# ProPrj_RS485_to_TTL_Converter_2026-02-24.net
KiCad netlist of a schematic drawn in EasyEDA Pro
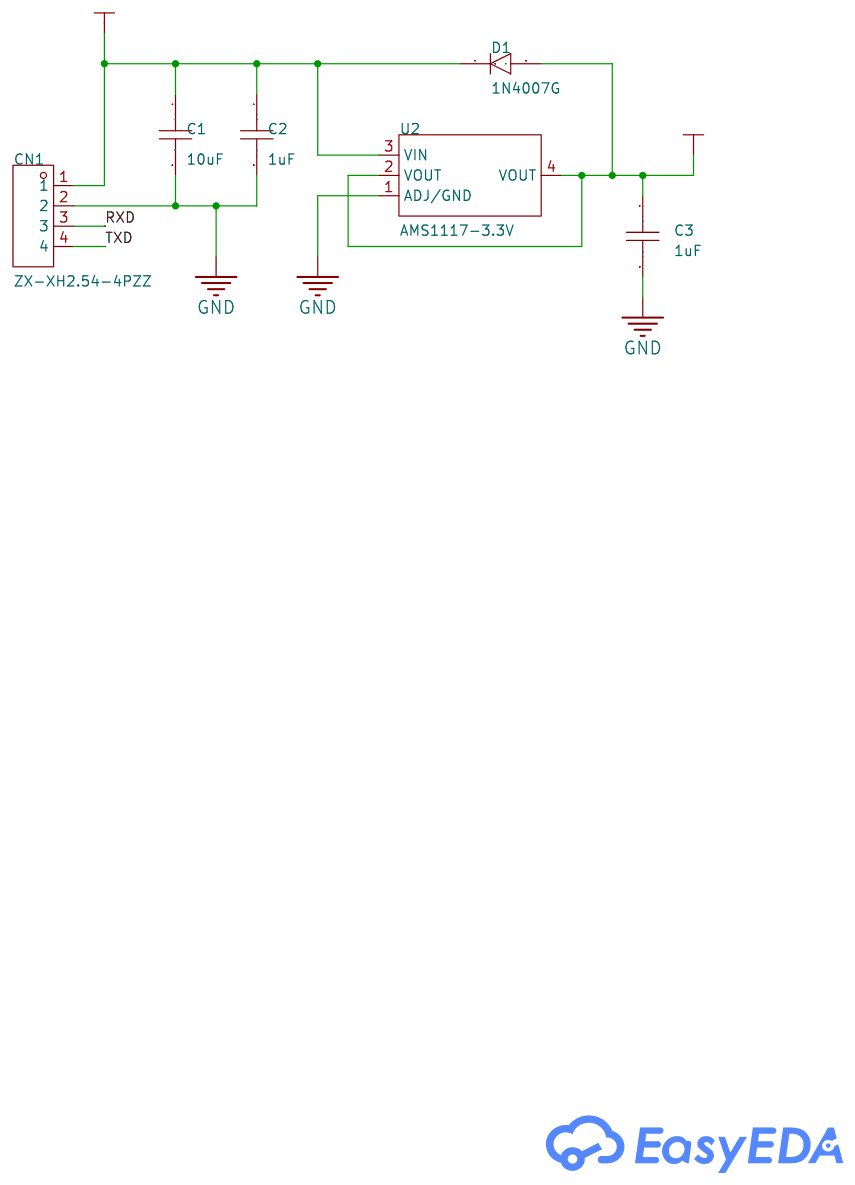
[diagram p0: Power Supply]
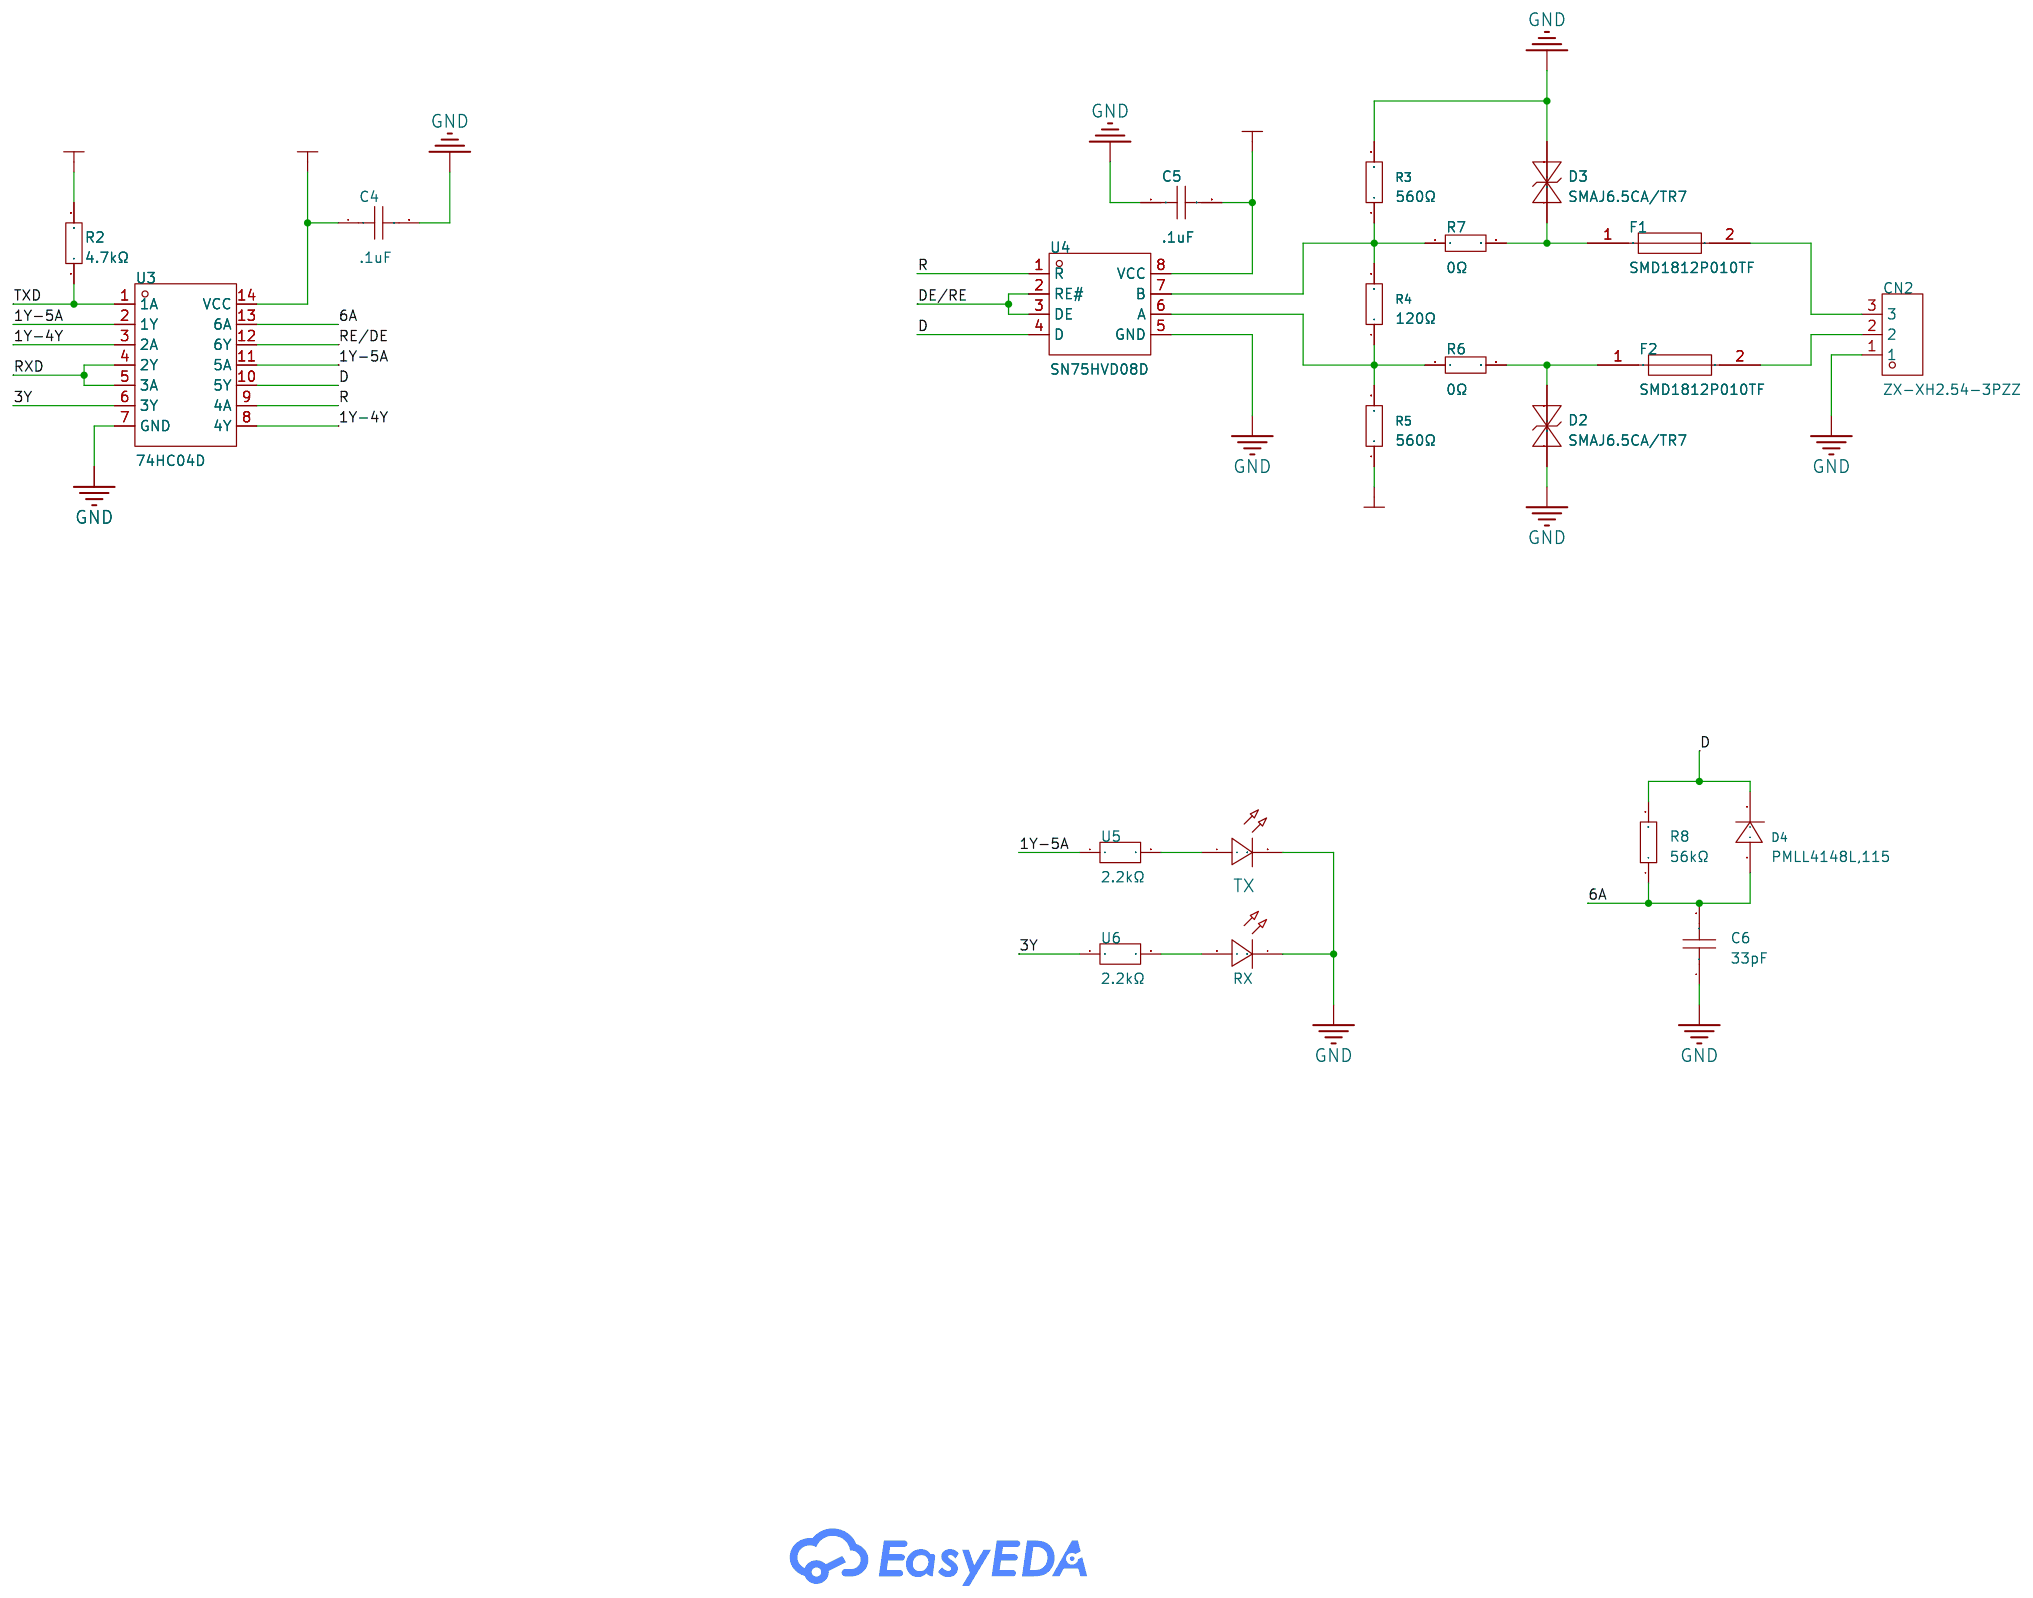
[diagram p1: RS485]

(export (version "E")
  (design (tool "Eeschema 10.0.6"))
  (components
    (comp (ref "C1")
      (value "10uF")
      (footprint "easyedapro:C0603")
      (libsource (lib "easyedapro") (part "CAP"))
    )
    (comp (ref "C2") (value "1uF") (footprint "easyedapro:C0603") (libsource (lib "easyedapro") (part "CAP")))
    (comp (ref "C3") (value "1uF") (footprint "easyedapro:C0603") (libsource (lib "easyedapro") (part "CAP")))
    (comp (ref "CN1")
      (value "ZX-XH2.54-4PZZ")
      (footprint "easyedapro:CONN-TH_4P-P2.50_4PIN")
      (fields (field (name "Manufacturer") "Megastar(兆星)"))
      (libsource (lib "easyedapro") (part "ZX-XH2.54-4PZZ"))
    )
    (comp (ref "D1")
      (value "1N4007G")
      (footprint "easyedapro:SMA_L4.4-W2.6-LS5.0-RD")
      (fields (field (name "Manufacturer") "SHIKUES(时科)"))
      (libsource (lib "easyedapro") (part "1N4007G"))
    )
    (comp (ref "U2")
      (value "AMS1117-3.3V")
      (footprint "easyedapro:SOT-223-4_L6.5-W3.5-P2.30-LS7.0-BR")
      (fields (field (name "Manufacturer") "WPMtek(维攀)"))
      (libsource (lib "easyedapro") (part "AMS1117-3.3V"))
    )
    (comp (ref "C4")
      (value ".1uF")
      (footprint "easyedapro:C0603")
      (libsource (lib "easyedapro") (part "CAP"))
    )
    (comp (ref "C5")
      (value ".1uF")
      (footprint "easyedapro:C0603")
      (libsource (lib "easyedapro") (part "CAP"))
    )
    (comp (ref "C6")
      (value "33pF")
      (footprint "easyedapro:C0603")
      (libsource (lib "easyedapro") (part "CAP"))
    )
    (comp (ref "CN2")
      (value "ZX-XH2.54-3PZZ")
      (footprint "easyedapro:CONN-TH_3P-P2.54_2501S-3P")
      (fields (field (name "Manufacturer") "Megastar(兆星)"))
      (libsource (lib "easyedapro") (part "ZX-XH2.54-3PZZ"))
    )
    (comp (ref "D2")
      (value "SMAJ6.5CA/TR7")
      (footprint "easyedapro:SMA_L4.3-W2.6-LS5.1-BI")
      (fields (field (name "Manufacturer") "Brightking(君耀电子)"))
      (libsource (lib "easyedapro") (part "SMAJ6.5CA/TR7"))
    )
    (comp (ref "D3")
      (value "SMAJ6.5CA/TR7")
      (footprint "easyedapro:SMA_L4.3-W2.6-LS5.1-BI")
      (fields (field (name "Manufacturer") "Brightking(君耀电子)"))
      (libsource (lib "easyedapro") (part "SMAJ6.5CA/TR7"))
    )
    (comp (ref "D4")
      (value "PMLL4148L,115")
      (footprint "easyedapro:SOD-80_L3.5-W1.5-RD")
      (fields (field (name "Manufacturer") "Nexperia(安世)"))
      (libsource (lib "easyedapro") (part "PMLL4148L,115"))
    )
    (comp (ref "F1")
      (value "SMD1812P010TF")
      (footprint "easyedapro:F1812")
      (fields (field (name "Manufacturer") "PTTC(聚鼎)"))
      (libsource (lib "easyedapro") (part "SMD1812P010TF_C495355"))
    )
    (comp (ref "F2")
      (value "SMD1812P010TF")
      (footprint "easyedapro:F1812")
      (fields (field (name "Manufacturer") "PTTC(聚鼎)"))
      (libsource (lib "easyedapro") (part "SMD1812P010TF_C495355"))
    )
    (comp (ref "R2")
      (value "4.7kΩ")
      (footprint "easyedapro:R0805")
      (fields
        (field (name "Manufacturer Part") "0805W8F4701T5E")
        (field (name "Manufacturer") "UNI-ROYAL(厚声)")
      )
      (libsource (lib "easyedapro") (part "0805W8F4701T5E"))
    )
    (comp (ref "R3")
      (value "560Ω")
      (footprint "easyedapro:R0805")
      (fields
        (field (name "Manufacturer Part") "0805W8F5600T5E")
        (field (name "Manufacturer") "UNI-ROYAL(厚声)")
      )
      (libsource (lib "easyedapro") (part "0805W8F5600T5E"))
    )
    (comp (ref "R4")
      (value "120Ω")
      (footprint "easyedapro:R0805")
      (fields
        (field (name "Manufacturer Part") "0805W8F1200T5E")
        (field (name "Manufacturer") "UNI-ROYAL(厚声)")
      )
      (libsource (lib "easyedapro") (part "0805W8F1200T5E"))
    )
    (comp (ref "R5")
      (value "560Ω")
      (footprint "easyedapro:R0805")
      (fields
        (field (name "Manufacturer Part") "0805W8F5600T5E")
        (field (name "Manufacturer") "UNI-ROYAL(厚声)")
      )
      (libsource (lib "easyedapro") (part "0805W8F5600T5E"))
    )
    (comp (ref "R6")
      (value "0Ω")
      (footprint "easyedapro:R0805")
      (fields
        (field (name "Manufacturer Part") "0805W8F0000T5E")
        (field (name "Manufacturer") "UNI-ROYAL(厚声)")
      )
      (libsource (lib "easyedapro") (part "0805W8F0000T5E"))
    )
    (comp (ref "R7")
      (value "0Ω")
      (footprint "easyedapro:R0805")
      (fields
        (field (name "Manufacturer Part") "0805W8F0000T5E")
        (field (name "Manufacturer") "UNI-ROYAL(厚声)")
      )
      (libsource (lib "easyedapro") (part "0805W8F0000T5E"))
    )
    (comp (ref "R8")
      (value "56kΩ")
      (footprint "easyedapro:R0805")
      (fields
        (field (name "Manufacturer Part") "0805W8F5602T5E")
        (field (name "Manufacturer") "UNI-ROYAL(厚声)")
      )
      (libsource (lib "easyedapro") (part "0805W8F5602T5E"))
    )
    (comp (ref "RX")
      (value "~")
      (footprint "easyedapro:LED0603-RD_GREEN")
      (libsource (lib "easyedapro") (part "LED_G"))
    )
    (comp (ref "TX")
      (value "~")
      (footprint "easyedapro:LED0603-R-RD")
      (libsource (lib "easyedapro") (part "LED_R"))
    )
    (comp (ref "U3")
      (value "74HC04D")
      (footprint "easyedapro:SOP-14_L8.6-W3.9-P1.27-LS6.0-BL")
      (fields (field (name "Manufacturer") "HTC"))
      (libsource (lib "easyedapro") (part "74HC04D"))
    )
    (comp (ref "U4")
      (value "SN75HVD08D")
      (footprint "easyedapro:SOIC-8_L4.9-W3.9-P1.27-LS6.0-BL")
      (fields (field (name "Manufacturer") "TI(德州仪器)"))
      (libsource (lib "easyedapro") (part "SN75HVD08D"))
    )
    (comp (ref "U5")
      (value "2.2kΩ")
      (footprint "easyedapro:R0805")
      (fields (field (name "Manufacturer Part") "FRC0805J222 TS") (field (name "Manufacturer") "FOJAN(富捷)"))
      (libsource (lib "easyedapro") (part "FRC0805J222 TS"))
    )
    (comp (ref "U6")
      (value "2.2kΩ")
      (footprint "easyedapro:R0805")
      (fields (field (name "Manufacturer Part") "FRC0805J222 TS") (field (name "Manufacturer") "FOJAN(富捷)"))
      (libsource (lib "easyedapro") (part "FRC0805J222 TS"))
    )
  )
  (nets
    (net (code "1") (name "1Y-4Y") (class "Default")
      (node (ref "U3") (pin "3") (pinfunction "2A_3") (pintype "unspecified"))
      (node (ref "U3") (pin "8") (pinfunction "4Y_8") (pintype "unspecified"))
    )
    (net (code "2") (name "1Y-5A") (class "Default")
      (node (ref "U3") (pin "11") (pinfunction "5A_11") (pintype "unspecified"))
      (node (ref "U3") (pin "2") (pinfunction "1Y_2") (pintype "unspecified"))
      (node (ref "U5") (pin "1") (pinfunction "1_1") (pintype "unspecified"))
    )
    (net (code "3") (name "3V3") (class "Default")
      (node (ref "C3") (pin "1") (pinfunction "1_1") (pintype "input"))
      (node (ref "C4") (pin "1") (pinfunction "1_1") (pintype "input"))
      (node (ref "C5") (pin "2") (pinfunction "2_2") (pintype "input"))
      (node (ref "D1") (pin "2") (pinfunction "A_2") (pintype "unspecified"))
      (node (ref "R2") (pin "2") (pinfunction "2_2") (pintype "input"))
      (node (ref "R5") (pin "1") (pinfunction "1_1") (pintype "input"))
      (node (ref "U2") (pin "2") (pinfunction "VOUT_2") (pintype "unspecified"))
      (node (ref "U2") (pin "4") (pinfunction "VOUT_4") (pintype "unspecified"))
      (node (ref "U3") (pin "14") (pinfunction "VCC_14") (pintype "unspecified"))
      (node (ref "U4") (pin "8") (pinfunction "VCC_8") (pintype "unspecified"))
    )
    (net (code "4") (name "3Y") (class "Default")
      (node (ref "U3") (pin "6") (pinfunction "3Y_6") (pintype "unspecified"))
      (node (ref "U6") (pin "1") (pinfunction "1_1") (pintype "unspecified"))
    )
    (net (code "5") (name "5V") (class "Default")
      (node (ref "C1") (pin "1") (pinfunction "1_1") (pintype "input"))
      (node (ref "C2") (pin "1") (pinfunction "1_1") (pintype "input"))
      (node (ref "CN1") (pin "1") (pinfunction "1_1") (pintype "unspecified"))
      (node (ref "D1") (pin "1") (pinfunction "C_1") (pintype "unspecified"))
      (node (ref "U2") (pin "3") (pinfunction "VIN_3") (pintype "unspecified"))
    )
    (net (code "6") (name "6A") (class "Default")
      (node (ref "C6") (pin "2") (pinfunction "2_2") (pintype "input"))
      (node (ref "D4") (pin "2") (pinfunction "A_2") (pintype "input"))
      (node (ref "R8") (pin "1") (pinfunction "1_1") (pintype "input"))
      (node (ref "U3") (pin "13") (pinfunction "6A_13") (pintype "unspecified"))
    )
    (net (code "7") (name "D") (class "Default")
      (node (ref "D4") (pin "1") (pinfunction "K_1") (pintype "input"))
      (node (ref "R8") (pin "2") (pinfunction "2_2") (pintype "input"))
      (node (ref "U3") (pin "10") (pinfunction "5Y_10") (pintype "unspecified"))
      (node (ref "U4") (pin "4") (pinfunction "D_4") (pintype "unspecified"))
    )
    (net (code "8") (name "DE{slash}RE") (class "Default")
      (node (ref "U4") (pin "2") (pinfunction "RE#_2") (pintype "unspecified"))
      (node (ref "U4") (pin "3") (pinfunction "DE_3") (pintype "unspecified"))
    )
    (net (code "9") (name "GND") (class "Default")
      (node (ref "C1") (pin "2") (pinfunction "2_2") (pintype "input"))
      (node (ref "C2") (pin "2") (pinfunction "2_2") (pintype "input"))
      (node (ref "C3") (pin "2") (pinfunction "2_2") (pintype "input"))
      (node (ref "C4") (pin "2") (pinfunction "2_2") (pintype "input"))
      (node (ref "C5") (pin "1") (pinfunction "1_1") (pintype "input"))
      (node (ref "C6") (pin "1") (pinfunction "1_1") (pintype "input"))
      (node (ref "CN1") (pin "2") (pinfunction "2_2") (pintype "unspecified"))
      (node (ref "CN2") (pin "1") (pinfunction "1_1") (pintype "unspecified"))
      (node (ref "D2") (pin "1") (pinfunction "1_1") (pintype "unspecified"))
      (node (ref "D3") (pin "2") (pinfunction "2_2") (pintype "unspecified"))
      (node (ref "R3") (pin "2") (pinfunction "2_2") (pintype "input"))
      (node (ref "RX") (pin "1") (pinfunction "C_1") (pintype "input"))
      (node (ref "TX") (pin "2") (pinfunction "C_2") (pintype "input"))
      (node (ref "U2") (pin "1") (pinfunction "ADJ/GND_1") (pintype "unspecified"))
      (node (ref "U3") (pin "7") (pinfunction "GND_7") (pintype "unspecified"))
      (node (ref "U4") (pin "5") (pinfunction "GND_5") (pintype "unspecified"))
    )
    (net (code "10") (name "Net-(CN2-Pad2)") (class "Default")
      (node (ref "CN2") (pin "2") (pinfunction "2_2") (pintype "unspecified"))
      (node (ref "F2") (pin "2") (pinfunction "2_2") (pintype "unspecified"))
    )
    (net (code "11") (name "Net-(CN2-Pad3)") (class "Default")
      (node (ref "CN2") (pin "3") (pinfunction "3_3") (pintype "unspecified"))
      (node (ref "F1") (pin "2") (pinfunction "2_2") (pintype "unspecified"))
    )
    (net (code "12") (name "Net-(D2-Pad2)") (class "Default")
      (node (ref "D2") (pin "2") (pinfunction "2_2") (pintype "unspecified"))
      (node (ref "F2") (pin "1") (pinfunction "1_1") (pintype "unspecified"))
      (node (ref "R6") (pin "2") (pinfunction "2_2") (pintype "input"))
    )
    (net (code "13") (name "Net-(D3-Pad1)") (class "Default")
      (node (ref "D3") (pin "1") (pinfunction "1_1") (pintype "unspecified"))
      (node (ref "F1") (pin "1") (pinfunction "1_1") (pintype "unspecified"))
      (node (ref "R7") (pin "2") (pinfunction "2_2") (pintype "input"))
    )
    (net (code "14") (name "Net-(RX-A)") (class "Default")
      (node (ref "RX") (pin "2") (pinfunction "A_2") (pintype "input"))
      (node (ref "U6") (pin "2") (pinfunction "2_2") (pintype "unspecified"))
    )
    (net (code "15") (name "Net-(TX-A)") (class "Default")
      (node (ref "TX") (pin "1") (pinfunction "A_1") (pintype "input"))
      (node (ref "U5") (pin "2") (pinfunction "2_2") (pintype "unspecified"))
    )
    (net (code "16") (name "Net-(U4-A)") (class "Default")
      (node (ref "R4") (pin "1") (pinfunction "1_1") (pintype "input"))
      (node (ref "R5") (pin "2") (pinfunction "2_2") (pintype "input"))
      (node (ref "R6") (pin "1") (pinfunction "1_1") (pintype "input"))
      (node (ref "U4") (pin "6") (pinfunction "A_6") (pintype "unspecified"))
    )
    (net (code "17") (name "Net-(U4-B)") (class "Default")
      (node (ref "R3") (pin "1") (pinfunction "1_1") (pintype "input"))
      (node (ref "R4") (pin "2") (pinfunction "2_2") (pintype "input"))
      (node (ref "R7") (pin "1") (pinfunction "1_1") (pintype "input"))
      (node (ref "U4") (pin "7") (pinfunction "B_7") (pintype "unspecified"))
    )
    (net (code "18") (name "R") (class "Default")
      (node (ref "U3") (pin "9") (pinfunction "4A_9") (pintype "unspecified"))
      (node (ref "U4") (pin "1") (pinfunction "R_1") (pintype "unspecified"))
    )
    (net (code "19") (name "RE{slash}DE") (class "Default")
      (node (ref "U3") (pin "12") (pinfunction "6Y_12") (pintype "unspecified"))
    )
    (net (code "20") (name "RXD") (class "Default")
      (node (ref "CN1") (pin "3") (pinfunction "3_3") (pintype "unspecified"))
      (node (ref "U3") (pin "4") (pinfunction "2Y_4") (pintype "unspecified"))
      (node (ref "U3") (pin "5") (pinfunction "3A_5") (pintype "unspecified"))
    )
    (net (code "21") (name "TXD") (class "Default")
      (node (ref "CN1") (pin "4") (pinfunction "4_4") (pintype "unspecified"))
      (node (ref "R2") (pin "1") (pinfunction "1_1") (pintype "input"))
      (node (ref "U3") (pin "1") (pinfunction "1A_1") (pintype "unspecified"))
    )
  )
)
